# Heater_Driver_BREAKOUT.net
KiCad netlist of a schematic drawn in EAGLE
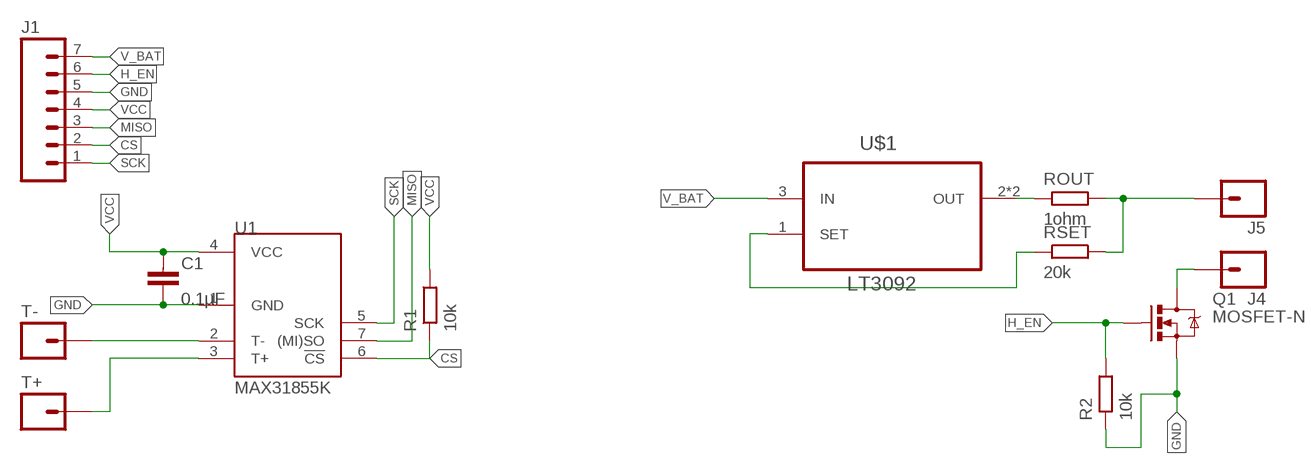
[diagram p0: schematic, sheet 1]

(export (version "E")
  (design (tool "Eeschema 10.0.6"))
  (components
    (comp (ref "C1")
      (value "0.1µF")
      (footprint "eagle-import:C0603-N")
      (libsource (lib "eagle-import") (part "CAPACITOR0603-N"))
    )
    (comp (ref "J1")
      (value "M07")
      (footprint "eagle-import:1X07")
      (libsource (lib "eagle-import") (part "M07"))
    )
    (comp (ref "J4")
      (value "M01SMD")
      (footprint "eagle-import:LUXEON-PAD")
      (libsource (lib "eagle-import") (part "M01SMD"))
    )
    (comp (ref "J5")
      (value "M01SMD")
      (footprint "eagle-import:LUXEON-PAD")
      (libsource (lib "eagle-import") (part "M01SMD"))
    )
    (comp (ref "Q1")
      (value "MOSFET-N")
      (footprint "eagle-import:SOT23-3")
      (libsource (lib "eagle-import") (part "MOSFET-NCHANNELAO3404A"))
    )
    (comp (ref "R1")
      (value "10k")
      (footprint "eagle-import:R0603-N")
      (libsource (lib "eagle-import") (part "RESISTOR0603-N"))
    )
    (comp (ref "R2")
      (value "10k")
      (footprint "eagle-import:R0603-N")
      (libsource (lib "eagle-import") (part "RESISTOR0603-N"))
    )
    (comp (ref "ROUT")
      (value "1ohm")
      (footprint "eagle-import:R0603-N")
      (libsource (lib "eagle-import") (part "RESISTOR0603-N"))
    )
    (comp (ref "RSET")
      (value "20k")
      (footprint "eagle-import:R0603-N")
      (libsource (lib "eagle-import") (part "RESISTOR0603-N"))
    )
    (comp (ref "T+")
      (value "M01SMD")
      (footprint "eagle-import:LUXEON-PAD")
      (libsource (lib "eagle-import") (part "M01SMD"))
    )
    (comp (ref "T-")
      (value "M01SMD")
      (footprint "eagle-import:LUXEON-PAD")
      (libsource (lib "eagle-import") (part "M01SMD"))
    )
    (comp (ref "U$1")
      (value "LT3092")
      (footprint "eagle-import:SOT223")
      (libsource (lib "eagle-import") (part "LT3092"))
    )
    (comp (ref "U1")
      (value "MAX31855K")
      (footprint "eagle-import:SOIC8")
      (libsource (lib "eagle-import") (part "MAX31855K"))
    )
  )
  (nets
    (net (code "1") (name "CS") (class "Default")
      (node (ref "J1") (pin "2") (pinfunction "2_2") (pintype "passive"))
      (node (ref "R1") (pin "1") (pinfunction "P$1_1") (pintype "passive"))
      (node (ref "U1") (pin "6") (pinfunction "~{CS}_6") (pintype "bidirectional"))
    )
    (net (code "2") (name "GND") (class "Default")
      (node (ref "C1") (pin "2") (pinfunction "2_2") (pintype "passive"))
      (node (ref "J1") (pin "5") (pinfunction "5_5") (pintype "passive"))
      (node (ref "Q1") (pin "2") (pinfunction "S_2") (pintype "passive"))
      (node (ref "R2") (pin "1") (pinfunction "P$1_1") (pintype "passive"))
      (node (ref "U1") (pin "1") (pinfunction "GND_1") (pintype "bidirectional"))
    )
    (net (code "3") (name "H_EN") (class "Default")
      (node (ref "J1") (pin "6") (pinfunction "6_6") (pintype "passive"))
      (node (ref "Q1") (pin "1") (pinfunction "G_1") (pintype "passive"))
      (node (ref "R2") (pin "2") (pinfunction "P$2_2") (pintype "passive"))
    )
    (net (code "4") (name "MISO") (class "Default")
      (node (ref "J1") (pin "3") (pinfunction "3_3") (pintype "passive"))
      (node (ref "U1") (pin "7") (pinfunction "(MI)SO_7") (pintype "bidirectional"))
    )
    (net (code "5") (name "Net-(J4-1)") (class "Default")
      (node (ref "J4") (pin "P$1") (pinfunction "1_P$1") (pintype "passive"))
      (node (ref "Q1") (pin "3") (pinfunction "D_3") (pintype "passive"))
    )
    (net (code "6") (name "Net-(J5-1)") (class "Default")
      (node (ref "J5") (pin "P$1") (pinfunction "1_P$1") (pintype "passive"))
      (node (ref "ROUT") (pin "2") (pinfunction "P$2_2") (pintype "passive"))
      (node (ref "RSET") (pin "2") (pinfunction "P$2_2") (pintype "passive"))
    )
    (net (code "7") (name "Net-(ROUT-P$1)") (class "Default")
      (node (ref "ROUT") (pin "1") (pinfunction "P$1_1") (pintype "passive"))
      (node (ref "U$1") (pin "2") (pinfunction "OUT_2") (pintype "output"))
      (node (ref "U$1") (pin "4") (pinfunction "OUT_4") (pintype "output"))
    )
    (net (code "8") (name "Net-(RSET-P$1)") (class "Default")
      (node (ref "RSET") (pin "1") (pinfunction "P$1_1") (pintype "passive"))
      (node (ref "U$1") (pin "1") (pinfunction "SET_1") (pintype "input"))
    )
    (net (code "9") (name "Net-(T+-1)") (class "Default")
      (node (ref "T+") (pin "P$1") (pinfunction "1_P$1") (pintype "passive"))
      (node (ref "U1") (pin "3") (pinfunction "T+_3") (pintype "bidirectional"))
    )
    (net (code "10") (name "Net-(T--1)") (class "Default")
      (node (ref "T-") (pin "P$1") (pinfunction "1_P$1") (pintype "passive"))
      (node (ref "U1") (pin "2") (pinfunction "T-_2") (pintype "bidirectional"))
    )
    (net (code "11") (name "SCK") (class "Default")
      (node (ref "J1") (pin "1") (pinfunction "1_1") (pintype "passive"))
      (node (ref "U1") (pin "5") (pinfunction "SCK_5") (pintype "bidirectional"))
    )
    (net (code "12") (name "VCC") (class "Default")
      (node (ref "C1") (pin "1") (pinfunction "1_1") (pintype "passive"))
      (node (ref "J1") (pin "4") (pinfunction "4_4") (pintype "passive"))
      (node (ref "R1") (pin "2") (pinfunction "P$2_2") (pintype "passive"))
      (node (ref "U1") (pin "4") (pinfunction "VCC_4") (pintype "bidirectional"))
    )
    (net (code "13") (name "V_BAT") (class "Default")
      (node (ref "J1") (pin "7") (pinfunction "7_7") (pintype "passive"))
      (node (ref "U$1") (pin "3") (pinfunction "IN_3") (pintype "power_in"))
    )
  )
)
